# SCH_SQIQ_pod_2022-06-01.net
KiCad netlist of a schematic drawn in EasyEDA
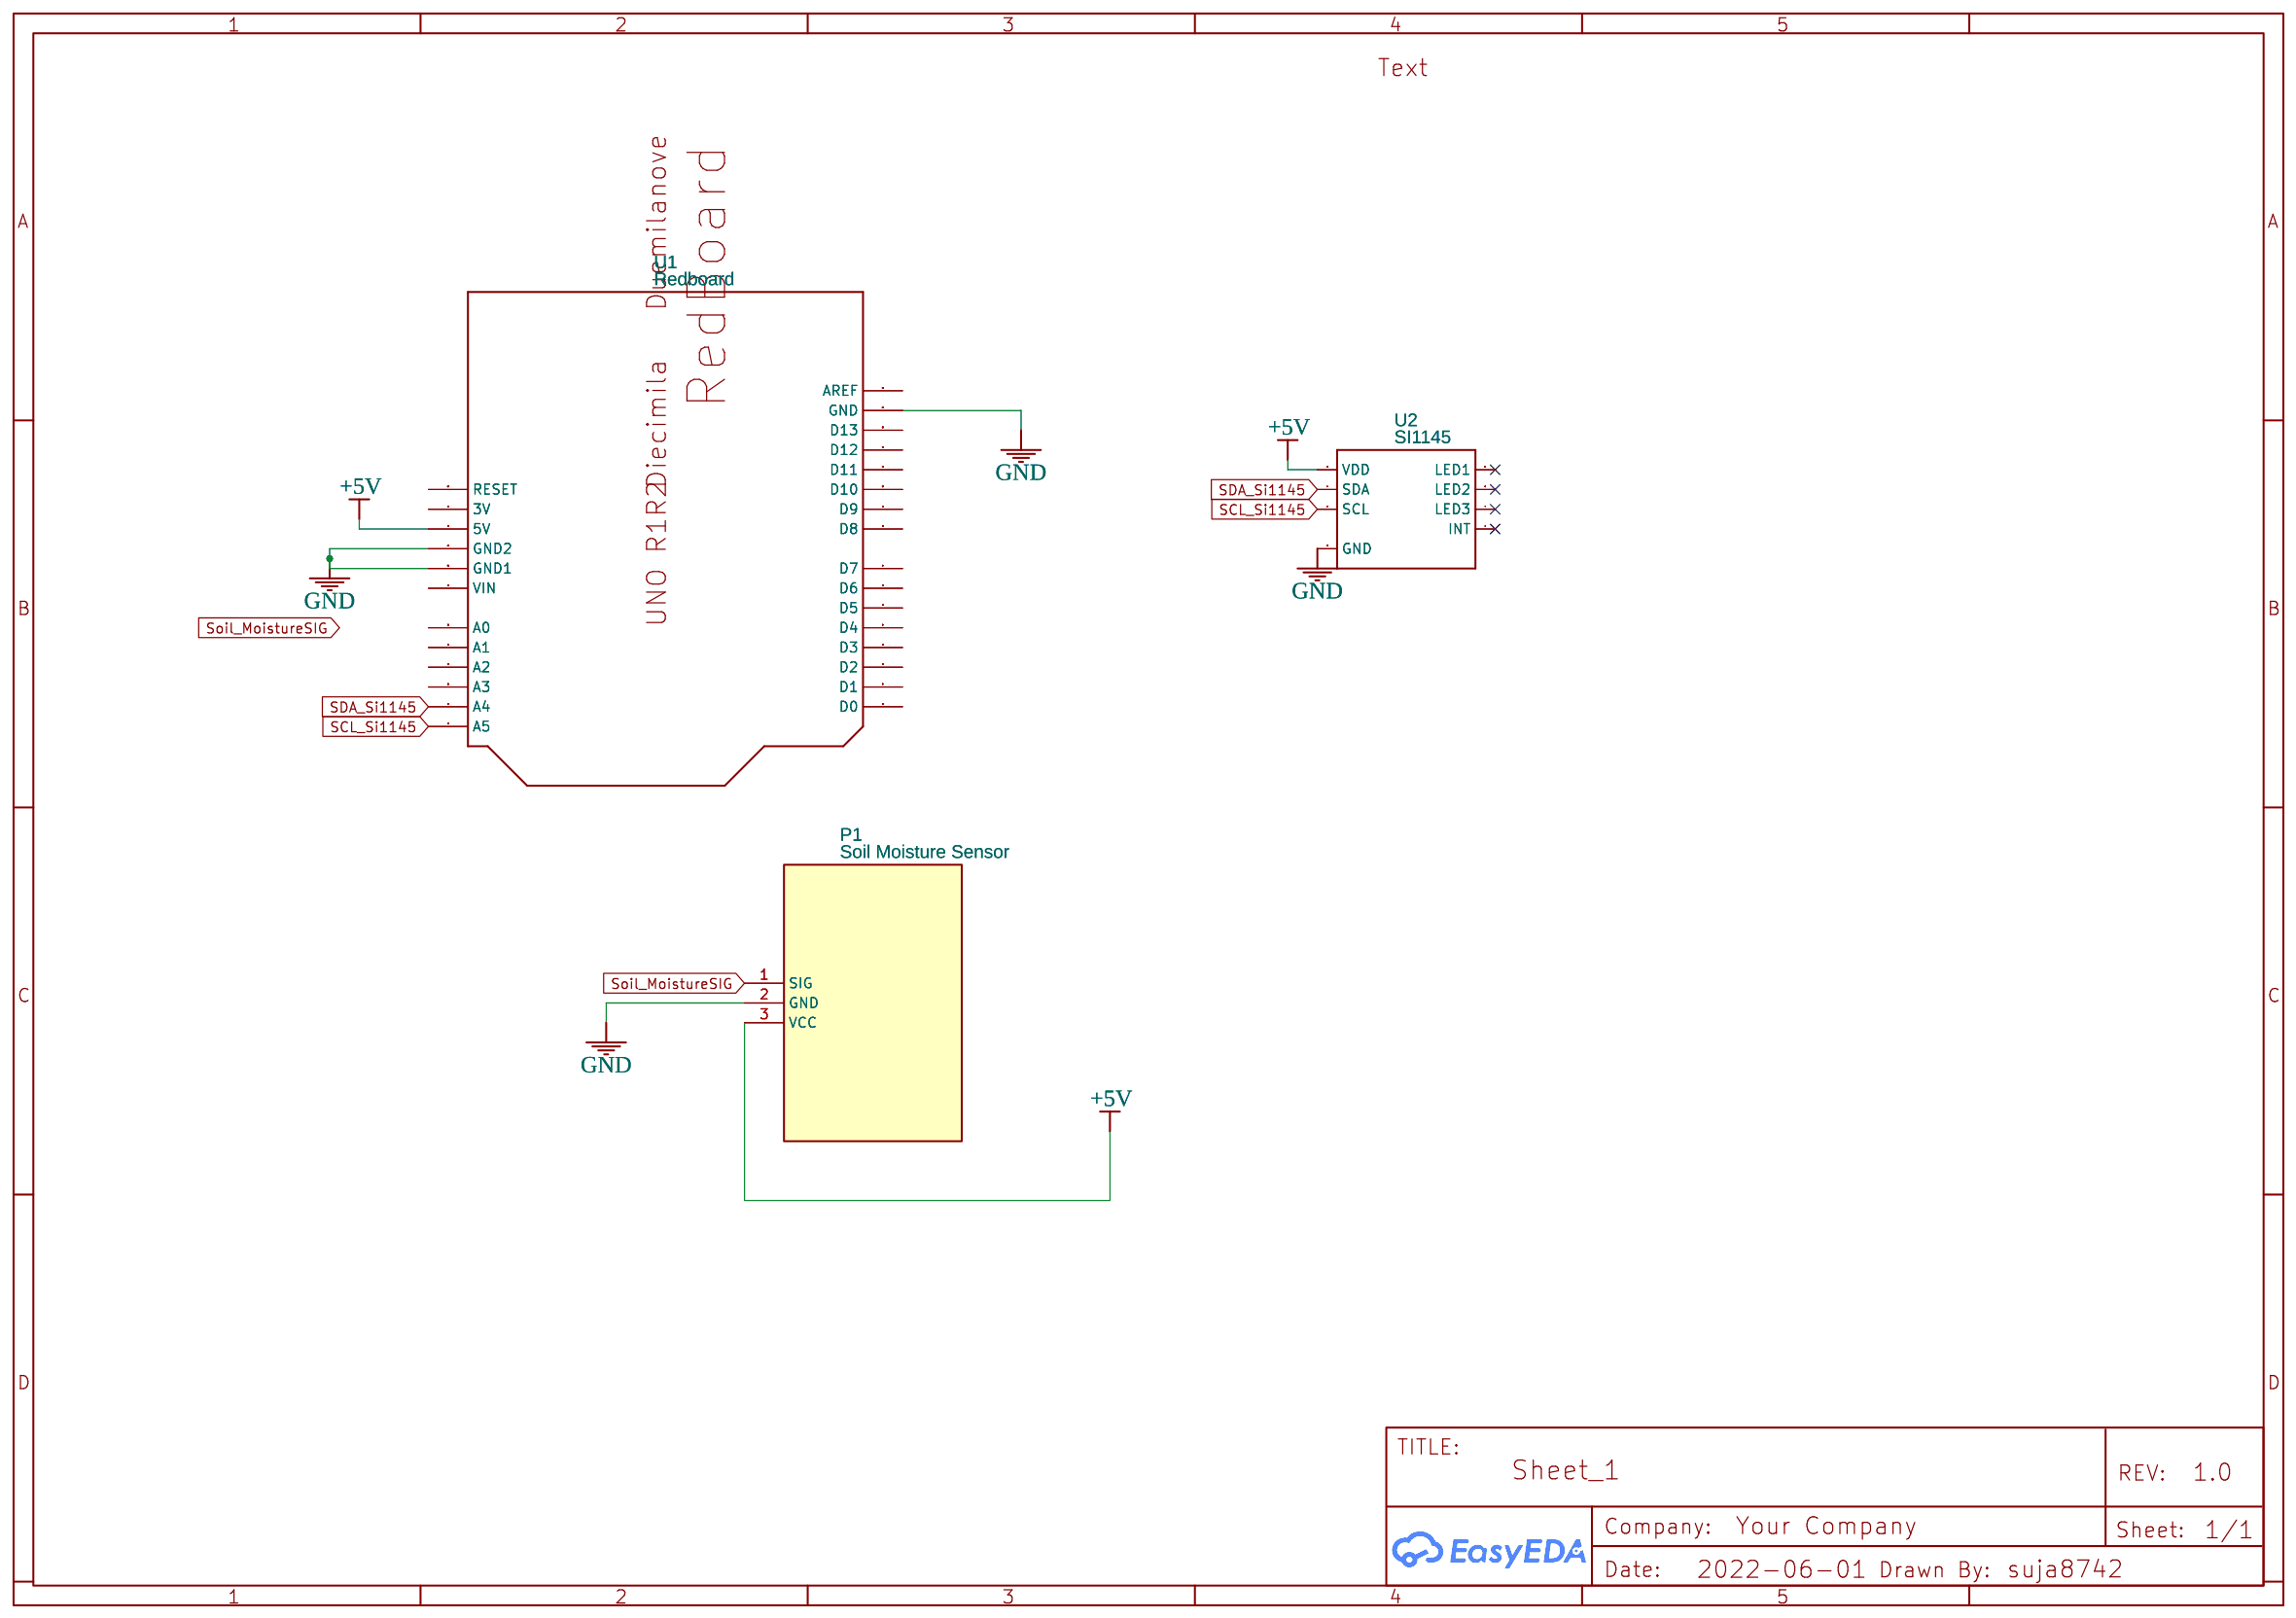
[diagram p0: schematic sheet]

(export (version "E")
  (design (tool "Eeschema 10.0.6"))
  (components
    (comp (ref "P1")
      (value "Soil Moisture Sensor")
      (fields (field (name "BOM_Supplier Part") "12587"))
      (libsource (lib "") (part "Soil Moisture Sensor"))
    )
    (comp (ref "U1") (value "Redboard") (libsource (lib "") (part "ARDUINOUNO")))
    (comp (ref "U2") (value "SI1145") (libsource (lib "") (part "SI1145")))
  )
  (nets
    (net (code "1") (name "+5V") (class "Default")
      (node (ref "P1") (pin "3") (pinfunction "VCC_3") (pintype "unspecified"))
      (node (ref "U1") (pin "5V") (pinfunction "5V_5V") (pintype "passive"))
      (node (ref "U2") (pin "3") (pinfunction "VDD_3") (pintype "unspecified"))
    )
    (net (code "2") (name "GND") (class "Default")
      (node (ref "P1") (pin "2") (pinfunction "GND_2") (pintype "unspecified"))
      (node (ref "U1") (pin "GND") (pinfunction "GND_GND") (pintype "passive"))
      (node (ref "U1") (pin "GND1") (pinfunction "GND1_GND1") (pintype "passive"))
      (node (ref "U1") (pin "GND2") (pinfunction "GND2_GND2") (pintype "passive"))
      (node (ref "U2") (pin "8") (pinfunction "GND_8") (pintype "unspecified"))
    )
    (net (code "3") (name "SCL_Si1145") (class "Default")
      (node (ref "U1") (pin "A5") (pinfunction "A5_A5") (pintype "unspecified"))
      (node (ref "U2") (pin "2") (pinfunction "SCL_2") (pintype "unspecified"))
    )
    (net (code "4") (name "SDA_Si1145") (class "Default")
      (node (ref "U1") (pin "A4") (pinfunction "A4_A4") (pintype "unspecified"))
      (node (ref "U2") (pin "1") (pinfunction "SDA_1") (pintype "unspecified"))
    )
    (net (code "5") (name "Soil_MoistureSIG") (class "Default")
      (node (ref "P1") (pin "1") (pinfunction "SIG_1") (pintype "unspecified"))
    )
    (net (code "6") (name "unconnected-(U1-Pad3V)") (class "Default")
      (node (ref "U1") (pin "3V") (pinfunction "3V_3V") (pintype "passive"))
    )
    (net (code "7") (name "unconnected-(U1-PadA0)") (class "Default")
      (node (ref "U1") (pin "A0") (pinfunction "A0_A0") (pintype "unspecified"))
    )
    (net (code "8") (name "unconnected-(U1-PadA1)") (class "Default")
      (node (ref "U1") (pin "A1") (pinfunction "A1_A1") (pintype "unspecified"))
    )
    (net (code "9") (name "unconnected-(U1-PadA2)") (class "Default")
      (node (ref "U1") (pin "A2") (pinfunction "A2_A2") (pintype "unspecified"))
    )
    (net (code "10") (name "unconnected-(U1-PadA3)") (class "Default")
      (node (ref "U1") (pin "A3") (pinfunction "A3_A3") (pintype "unspecified"))
    )
    (net (code "11") (name "unconnected-(U1-PadAREF)") (class "Default")
      (node (ref "U1") (pin "AREF") (pinfunction "AREF_AREF") (pintype "unspecified"))
    )
    (net (code "12") (name "unconnected-(U1-PadD0)") (class "Default")
      (node (ref "U1") (pin "D0") (pinfunction "D0_D0") (pintype "unspecified"))
    )
    (net (code "13") (name "unconnected-(U1-PadD1)") (class "Default")
      (node (ref "U1") (pin "D1") (pinfunction "D1_D1") (pintype "unspecified"))
    )
    (net (code "14") (name "unconnected-(U1-PadD2)") (class "Default")
      (node (ref "U1") (pin "D2") (pinfunction "D2_D2") (pintype "unspecified"))
    )
    (net (code "15") (name "unconnected-(U1-PadD3)") (class "Default")
      (node (ref "U1") (pin "D3") (pinfunction "D3_D3") (pintype "unspecified"))
    )
    (net (code "16") (name "unconnected-(U1-PadD4)") (class "Default")
      (node (ref "U1") (pin "D4") (pinfunction "D4_D4") (pintype "unspecified"))
    )
    (net (code "17") (name "unconnected-(U1-PadD5)") (class "Default")
      (node (ref "U1") (pin "D5") (pinfunction "D5_D5") (pintype "unspecified"))
    )
    (net (code "18") (name "unconnected-(U1-PadD6)") (class "Default")
      (node (ref "U1") (pin "D6") (pinfunction "D6_D6") (pintype "unspecified"))
    )
    (net (code "19") (name "unconnected-(U1-PadD7)") (class "Default")
      (node (ref "U1") (pin "D7") (pinfunction "D7_D7") (pintype "unspecified"))
    )
    (net (code "20") (name "unconnected-(U1-PadD8)") (class "Default")
      (node (ref "U1") (pin "D8") (pinfunction "D8_D8") (pintype "unspecified"))
    )
    (net (code "21") (name "unconnected-(U1-PadD9)") (class "Default")
      (node (ref "U1") (pin "D9") (pinfunction "D9_D9") (pintype "unspecified"))
    )
    (net (code "22") (name "unconnected-(U1-PadD10)") (class "Default")
      (node (ref "U1") (pin "D10") (pinfunction "D10_D10") (pintype "unspecified"))
    )
    (net (code "23") (name "unconnected-(U1-PadD11)") (class "Default")
      (node (ref "U1") (pin "D11") (pinfunction "D11_D11") (pintype "unspecified"))
    )
    (net (code "24") (name "unconnected-(U1-PadD12)") (class "Default")
      (node (ref "U1") (pin "D12") (pinfunction "D12_D12") (pintype "unspecified"))
    )
    (net (code "25") (name "unconnected-(U1-PadD13)") (class "Default")
      (node (ref "U1") (pin "D13") (pinfunction "D13_D13") (pintype "unspecified"))
    )
    (net (code "26") (name "unconnected-(U1-PadRESET)") (class "Default")
      (node (ref "U1") (pin "RESET") (pinfunction "RESET_RESET") (pintype "unspecified"))
    )
    (net (code "27") (name "unconnected-(U1-PadVIN)") (class "Default")
      (node (ref "U1") (pin "VIN") (pinfunction "VIN_VIN") (pintype "passive"))
    )
    (net (code "28") (name "unconnected-(U2-INT-Pad4)") (class "Default")
      (node (ref "U2") (pin "4") (pinfunction "INT_4") (pintype "unspecified+no_connect"))
    )
    (net (code "29") (name "unconnected-(U2-LED1-Pad9)") (class "Default")
      (node (ref "U2") (pin "9") (pinfunction "LED1_9") (pintype "unspecified+no_connect"))
    )
    (net (code "30") (name "unconnected-(U2-LED2-Pad6)") (class "Default")
      (node (ref "U2") (pin "6") (pinfunction "LED2_6") (pintype "unspecified+no_connect"))
    )
    (net (code "31") (name "unconnected-(U2-LED3-Pad7)") (class "Default")
      (node (ref "U2") (pin "7") (pinfunction "LED3_7") (pintype "unspecified+no_connect"))
    )
  )
)
